# main.net
KiCad netlist of a schematic drawn in Altium Designer
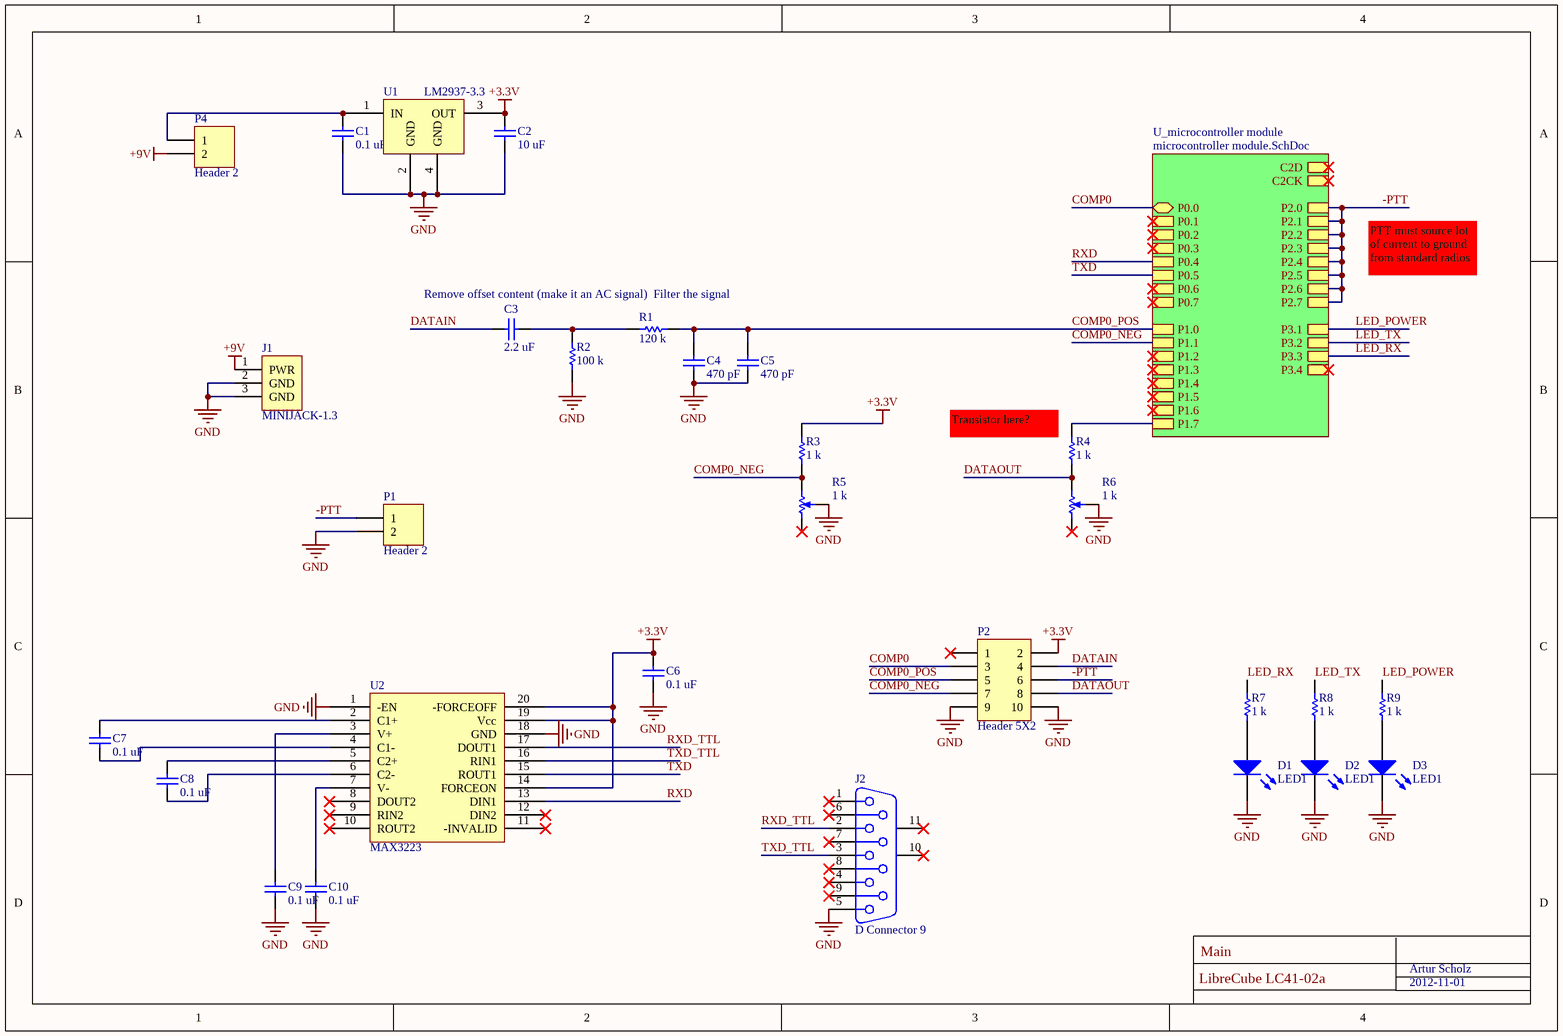
[diagram p0: main.SchDoc]

(export (version "E")
  (design (tool "Eeschema 10.0.6"))
  (components
    (comp (ref "C1")
      (value "0.1 uF")
      (footprint "0603")
      (description "Capacitor")
      (libsource (lib "allspace_schem") (part "Capacitor"))
    )
    (comp (ref "C2")
      (value "10 uF")
      (footprint "1206")
      (description "Capacitor")
      (libsource (lib "allspace_schem") (part "Capacitor"))
    )
    (comp (ref "C3")
      (value "2.2 uF")
      (footprint "0603")
      (description "Capacitor")
      (libsource (lib "allspace_schem") (part "Capacitor"))
    )
    (comp (ref "C4")
      (value "470 pF")
      (footprint "0603")
      (description "Capacitor")
      (libsource (lib "allspace_schem") (part "Capacitor"))
    )
    (comp (ref "C5")
      (value "470 pF")
      (footprint "0603")
      (description "Capacitor")
      (libsource (lib "allspace_schem") (part "Capacitor"))
    )
    (comp (ref "C6")
      (value "0.1 uF")
      (footprint "0603")
      (description "Capacitor")
      (libsource (lib "allspace_schem") (part "Capacitor"))
    )
    (comp (ref "C7")
      (value "0.1 uF")
      (footprint "0603")
      (description "Capacitor")
      (libsource (lib "allspace_schem") (part "Capacitor"))
    )
    (comp (ref "C8")
      (value "0.1 uF")
      (footprint "0603")
      (description "Capacitor")
      (libsource (lib "allspace_schem") (part "Capacitor"))
    )
    (comp (ref "C9")
      (value "0.1 uF")
      (footprint "0603")
      (description "Capacitor")
      (libsource (lib "allspace_schem") (part "Capacitor"))
    )
    (comp (ref "C10")
      (value "0.1 uF")
      (footprint "0603")
      (description "Capacitor")
      (libsource (lib "allspace_schem") (part "Capacitor"))
    )
    (comp (ref "D1")
      (value "LED1")
      (footprint "LED-1")
      (description "Typical RED GaAs LED")
      (fields (field (name "PUBLISHER") "Altium Limited"))
      (libsource (lib "Miscellaneous Devices") (part "LED1"))
    )
    (comp (ref "D2")
      (value "LED1")
      (footprint "LED-1")
      (description "Typical RED GaAs LED")
      (fields (field (name "PUBLISHER") "Altium Limited"))
      (libsource (lib "Miscellaneous Devices") (part "LED1"))
    )
    (comp (ref "D3")
      (value "LED1")
      (footprint "LED-1")
      (description "Typical RED GaAs LED")
      (fields (field (name "PUBLISHER") "Altium Limited"))
      (libsource (lib "Miscellaneous Devices") (part "LED1"))
    )
    (comp (ref "J1")
      (value "MINIJACK-1.3")
      (footprint "POWERJACK")
      (libsource (lib "allspace_schem") (part "PWRJACK-1.3"))
    )
    (comp (ref "J2")
      (value "D Connector 9")
      (footprint "DSUB1.385-2H9")
      (description "Receptacle Assembly, 9 Position, Right Angle")
      (fields (field (name "PUBLISHER") "Altium Limited"))
      (libsource (lib "Miscellaneous Connectors") (part "D Connector 9"))
    )
    (comp (ref "P1")
      (value "Header 2")
      (footprint "HDR1X2")
      (description "Header, 2-Pin")
      (fields (field (name "PUBLISHER") "Altium Limited"))
      (libsource (lib "allspace_schem") (part "Header 2"))
    )
    (comp (ref "P2")
      (value "Header 5X2")
      (footprint "HDR2X5")
      (description "Header, 5-Pin, Dual row")
      (fields (field (name "PUBLISHER") "Altium Limited"))
      (libsource (lib "allspace_schem") (part "Header 5X2"))
    )
    (comp (ref "P4")
      (value "Header 2")
      (footprint "HDR1X2")
      (description "Header, 2-Pin")
      (fields (field (name "PUBLISHER") "Altium Limited"))
      (libsource (lib "allspace_schem") (part "Header 2"))
    )
    (comp (ref "R1")
      (value "120 k")
      (footprint "0603")
      (description "Resistor")
      (libsource (lib "allspace_schem") (part "Resistor"))
    )
    (comp (ref "R2")
      (value "100 k")
      (footprint "0603")
      (description "Resistor")
      (libsource (lib "allspace_schem") (part "Resistor"))
    )
    (comp (ref "R3")
      (value "1 k")
      (footprint "0603")
      (description "Resistor")
      (libsource (lib "allspace_schem") (part "Resistor"))
    )
    (comp (ref "R4")
      (value "1 k")
      (footprint "0603")
      (description "Resistor")
      (libsource (lib "allspace_schem") (part "Resistor"))
    )
    (comp (ref "R5")
      (value "1 k")
      (footprint "POT4MM-2")
      (description "Square Trimming Potentiometer")
      (fields (field (name "PUBLISHER") "Altium Limited"))
      (libsource (lib "Miscellaneous Devices") (part "RPot SM"))
    )
    (comp (ref "R6")
      (value "1 k")
      (footprint "POT4MM-2")
      (description "Square Trimming Potentiometer")
      (fields (field (name "PUBLISHER") "Altium Limited"))
      (libsource (lib "Miscellaneous Devices") (part "RPot SM"))
    )
    (comp (ref "R7")
      (value "1 k")
      (footprint "0603")
      (description "Resistor")
      (libsource (lib "allspace_schem") (part "Resistor"))
    )
    (comp (ref "R8")
      (value "1 k")
      (footprint "0603")
      (description "Resistor")
      (libsource (lib "allspace_schem") (part "Resistor"))
    )
    (comp (ref "R9")
      (value "1 k")
      (footprint "0603")
      (description "Resistor")
      (libsource (lib "allspace_schem") (part "Resistor"))
    )
    (comp (ref "U1")
      (value "LM2937-3.3")
      (footprint "SOT-223")
      (description "LDO")
      (libsource (lib "allspace_schem") (part "LM2937"))
    )
    (comp (ref "U2")
      (value "MAX3223")
      (footprint "TSSOP-20")
      (libsource (lib "allspace_schem") (part "MAX3223"))
    )
  )
  (nets
    (net (code "1") (name "+3.3V") (class "Default")
      (node (ref "C2") (pin "2") (pinfunction "2_2") (pintype "passive"))
      (node (ref "C6") (pin "2") (pinfunction "2_2") (pintype "passive"))
      (node (ref "P2") (pin "2") (pinfunction "2_2") (pintype "passive"))
      (node (ref "R3") (pin "2") (pinfunction "2_2") (pintype "passive"))
      (node (ref "U1") (pin "3") (pinfunction "OUT_3") (pintype "passive"))
      (node (ref "U2") (pin "14") (pinfunction "FORCEON_14") (pintype "passive"))
      (node (ref "U2") (pin "19") (pinfunction "Vcc_19") (pintype "passive"))
      (node (ref "U2") (pin "20") (pinfunction "-FORCEOFF_20") (pintype "passive"))
    )
    (net (code "2") (name "+9V") (class "Default")
      (node (ref "J1") (pin "1") (pinfunction "PWR_1") (pintype "passive"))
      (node (ref "P4") (pin "2") (pinfunction "2_2") (pintype "passive"))
    )
    (net (code "3") (name "/-PTT") (class "Default")
      (node (ref "P1") (pin "1") (pinfunction "1_1") (pintype "passive"))
      (node (ref "P2") (pin "6") (pinfunction "6_6") (pintype "passive"))
    )
    (net (code "6") (name "/COMP0") (class "Default")
      (node (ref "P2") (pin "3") (pinfunction "3_3") (pintype "passive"))
    )
    (net (code "7") (name "/COMP0_NEG") (class "Default")
      (node (ref "P2") (pin "7") (pinfunction "7_7") (pintype "passive"))
      (node (ref "R3") (pin "1") (pinfunction "1_1") (pintype "passive"))
      (node (ref "R5") (pin "CW") (pinfunction "+_CW") (pintype "passive"))
    )
    (net (code "8") (name "/COMP0_POS") (class "Default")
      (node (ref "C4") (pin "2") (pinfunction "2_2") (pintype "passive"))
      (node (ref "C5") (pin "2") (pinfunction "2_2") (pintype "passive"))
      (node (ref "P2") (pin "5") (pinfunction "5_5") (pintype "passive"))
      (node (ref "R1") (pin "1") (pinfunction "1_1") (pintype "passive"))
    )
    (net (code "9") (name "/DATAIN") (class "Default")
      (node (ref "C3") (pin "1") (pinfunction "1_1") (pintype "passive"))
      (node (ref "P2") (pin "4") (pinfunction "4_4") (pintype "passive"))
    )
    (net (code "10") (name "/DATAOUT") (class "Default")
      (node (ref "P2") (pin "8") (pinfunction "8_8") (pintype "passive"))
      (node (ref "R4") (pin "1") (pinfunction "1_1") (pintype "passive"))
      (node (ref "R6") (pin "CW") (pinfunction "+_CW") (pintype "passive"))
    )
    (net (code "11") (name "/LED_POWER") (class "Default")
      (node (ref "R9") (pin "2") (pinfunction "2_2") (pintype "passive"))
    )
    (net (code "12") (name "/LED_RX") (class "Default")
      (node (ref "R7") (pin "2") (pinfunction "2_2") (pintype "passive"))
    )
    (net (code "13") (name "/LED_TX") (class "Default")
      (node (ref "R8") (pin "2") (pinfunction "2_2") (pintype "passive"))
    )
    (net (code "24") (name "/P1.7") (class "Default")
      (node (ref "R4") (pin "2") (pinfunction "2_2") (pintype "passive"))
    )
    (net (code "26") (name "/RXD") (class "Default")
      (node (ref "U2") (pin "13") (pinfunction "DIN1_13") (pintype "passive"))
    )
    (net (code "27") (name "/RXD_TTL") (class "Default")
      (node (ref "J2") (pin "2") (pinfunction "2_2") (pintype "passive"))
      (node (ref "U2") (pin "17") (pinfunction "DOUT1_17") (pintype "passive"))
    )
    (net (code "28") (name "/TXD") (class "Default")
      (node (ref "U2") (pin "15") (pinfunction "ROUT1_15") (pintype "passive"))
    )
    (net (code "29") (name "/TXD_TTL") (class "Default")
      (node (ref "J2") (pin "3") (pinfunction "3_3") (pintype "passive"))
      (node (ref "U2") (pin "16") (pinfunction "RIN1_16") (pintype "passive"))
    )
    (net (code "30") (name "GND") (class "Default")
      (node (ref "C1") (pin "1") (pinfunction "1_1") (pintype "passive"))
      (node (ref "C10") (pin "1") (pinfunction "1_1") (pintype "passive"))
      (node (ref "C2") (pin "1") (pinfunction "1_1") (pintype "passive"))
      (node (ref "C4") (pin "1") (pinfunction "1_1") (pintype "passive"))
      (node (ref "C5") (pin "1") (pinfunction "1_1") (pintype "passive"))
      (node (ref "C6") (pin "1") (pinfunction "1_1") (pintype "passive"))
      (node (ref "C9") (pin "2") (pinfunction "2_2") (pintype "passive"))
      (node (ref "D1") (pin "2") (pinfunction "K_2") (pintype "passive"))
      (node (ref "D2") (pin "2") (pinfunction "K_2") (pintype "passive"))
      (node (ref "D3") (pin "2") (pinfunction "K_2") (pintype "passive"))
      (node (ref "J1") (pin "2") (pinfunction "GND_2") (pintype "passive"))
      (node (ref "J1") (pin "3") (pinfunction "GND_3") (pintype "passive"))
      (node (ref "J2") (pin "5") (pinfunction "5_5") (pintype "passive"))
      (node (ref "P1") (pin "2") (pinfunction "2_2") (pintype "passive"))
      (node (ref "P2") (pin "10") (pinfunction "10_10") (pintype "passive"))
      (node (ref "P2") (pin "9") (pinfunction "9_9") (pintype "passive"))
      (node (ref "R2") (pin "1") (pinfunction "1_1") (pintype "passive"))
      (node (ref "R5") (pin "W") (pinfunction "W_W") (pintype "passive"))
      (node (ref "R6") (pin "W") (pinfunction "W_W") (pintype "passive"))
      (node (ref "U1") (pin "2") (pinfunction "GND_2") (pintype "passive"))
      (node (ref "U1") (pin "4") (pinfunction "GND_4") (pintype "passive"))
      (node (ref "U2") (pin "1") (pinfunction "-EN_1") (pintype "passive"))
      (node (ref "U2") (pin "18") (pinfunction "GND_18") (pintype "passive"))
    )
    (net (code "31") (name "Net-(C3-Pad2)") (class "Default")
      (node (ref "C3") (pin "2") (pinfunction "2_2") (pintype "passive"))
      (node (ref "R1") (pin "2") (pinfunction "2_2") (pintype "passive"))
      (node (ref "R2") (pin "2") (pinfunction "2_2") (pintype "passive"))
    )
    (net (code "32") (name "Net-(D1-A)") (class "Default")
      (node (ref "D1") (pin "1") (pinfunction "A_1") (pintype "passive"))
      (node (ref "R7") (pin "1") (pinfunction "1_1") (pintype "passive"))
    )
    (net (code "33") (name "Net-(D2-A)") (class "Default")
      (node (ref "D2") (pin "1") (pinfunction "A_1") (pintype "passive"))
      (node (ref "R8") (pin "1") (pinfunction "1_1") (pintype "passive"))
    )
    (net (code "34") (name "Net-(D3-A)") (class "Default")
      (node (ref "D3") (pin "1") (pinfunction "A_1") (pintype "passive"))
      (node (ref "R9") (pin "1") (pinfunction "1_1") (pintype "passive"))
    )
    (net (code "35") (name "Net-(U1-IN)") (class "Default")
      (node (ref "C1") (pin "2") (pinfunction "2_2") (pintype "passive"))
      (node (ref "P4") (pin "1") (pinfunction "1_1") (pintype "passive"))
      (node (ref "U1") (pin "1") (pinfunction "IN_1") (pintype "passive"))
    )
    (net (code "36") (name "Net-(U2-C1+)") (class "Default")
      (node (ref "C7") (pin "1") (pinfunction "1_1") (pintype "passive"))
      (node (ref "U2") (pin "2") (pinfunction "C1+_2") (pintype "passive"))
    )
    (net (code "37") (name "Net-(U2-C1-)") (class "Default")
      (node (ref "C7") (pin "2") (pinfunction "2_2") (pintype "passive"))
      (node (ref "U2") (pin "4") (pinfunction "C1-_4") (pintype "passive"))
    )
    (net (code "38") (name "Net-(U2-C2+)") (class "Default")
      (node (ref "C8") (pin "2") (pinfunction "2_2") (pintype "passive"))
      (node (ref "U2") (pin "5") (pinfunction "C2+_5") (pintype "passive"))
    )
    (net (code "39") (name "Net-(U2-C2-)") (class "Default")
      (node (ref "C8") (pin "1") (pinfunction "1_1") (pintype "passive"))
      (node (ref "U2") (pin "6") (pinfunction "C2-_6") (pintype "passive"))
    )
    (net (code "40") (name "Net-(U2-V+)") (class "Default")
      (node (ref "C9") (pin "1") (pinfunction "1_1") (pintype "passive"))
      (node (ref "U2") (pin "3") (pinfunction "V+_3") (pintype "passive"))
    )
    (net (code "41") (name "Net-(U2-V-)") (class "Default")
      (node (ref "C10") (pin "2") (pinfunction "2_2") (pintype "passive"))
      (node (ref "U2") (pin "7") (pinfunction "V-_7") (pintype "passive"))
    )
    (net (code "42") (name "unconnected-(J2-MH1-Pad10)") (class "Default")
      (node (ref "J2") (pin "10") (pinfunction "MH1_10") (pintype "passive+no_connect"))
    )
    (net (code "43") (name "unconnected-(J2-MH2-Pad11)") (class "Default")
      (node (ref "J2") (pin "11") (pinfunction "MH2_11") (pintype "passive+no_connect"))
    )
    (net (code "44") (name "unconnected-(J2-Pad1)") (class "Default")
      (node (ref "J2") (pin "1") (pinfunction "1_1") (pintype "passive+no_connect"))
    )
    (net (code "45") (name "unconnected-(J2-Pad4)") (class "Default")
      (node (ref "J2") (pin "4") (pinfunction "4_4") (pintype "passive+no_connect"))
    )
    (net (code "46") (name "unconnected-(J2-Pad6)") (class "Default")
      (node (ref "J2") (pin "6") (pinfunction "6_6") (pintype "passive+no_connect"))
    )
    (net (code "47") (name "unconnected-(J2-Pad7)") (class "Default")
      (node (ref "J2") (pin "7") (pinfunction "7_7") (pintype "passive+no_connect"))
    )
    (net (code "48") (name "unconnected-(J2-Pad8)") (class "Default")
      (node (ref "J2") (pin "8") (pinfunction "8_8") (pintype "passive+no_connect"))
    )
    (net (code "49") (name "unconnected-(J2-Pad9)") (class "Default")
      (node (ref "J2") (pin "9") (pinfunction "9_9") (pintype "passive+no_connect"))
    )
    (net (code "50") (name "unconnected-(P2-Pad1)") (class "Default")
      (node (ref "P2") (pin "1") (pinfunction "1_1") (pintype "passive+no_connect"))
    )
    (net (code "51") (name "unconnected-(R5---PadCCW)") (class "Default")
      (node (ref "R5") (pin "CCW") (pinfunction "-_CCW") (pintype "passive+no_connect"))
    )
    (net (code "52") (name "unconnected-(R6---PadCCW)") (class "Default")
      (node (ref "R6") (pin "CCW") (pinfunction "-_CCW") (pintype "passive+no_connect"))
    )
    (net (code "53") (name "unconnected-(U2--INVALID-Pad11)") (class "Default")
      (node (ref "U2") (pin "11") (pinfunction "-INVALID_11") (pintype "passive+no_connect"))
    )
    (net (code "54") (name "unconnected-(U2-DIN2-Pad12)") (class "Default")
      (node (ref "U2") (pin "12") (pinfunction "DIN2_12") (pintype "passive+no_connect"))
    )
    (net (code "55") (name "unconnected-(U2-DOUT2-Pad8)") (class "Default")
      (node (ref "U2") (pin "8") (pinfunction "DOUT2_8") (pintype "passive+no_connect"))
    )
    (net (code "56") (name "unconnected-(U2-RIN2-Pad9)") (class "Default")
      (node (ref "U2") (pin "9") (pinfunction "RIN2_9") (pintype "passive+no_connect"))
    )
    (net (code "57") (name "unconnected-(U2-ROUT2-Pad10)") (class "Default")
      (node (ref "U2") (pin "10") (pinfunction "ROUT2_10") (pintype "passive+no_connect"))
    )
  )
)
